# ESP8266_1wire_Gateway_NodeMCU_WeMosD1Min.net
KiCad netlist of a schematic drawn in EAGLE
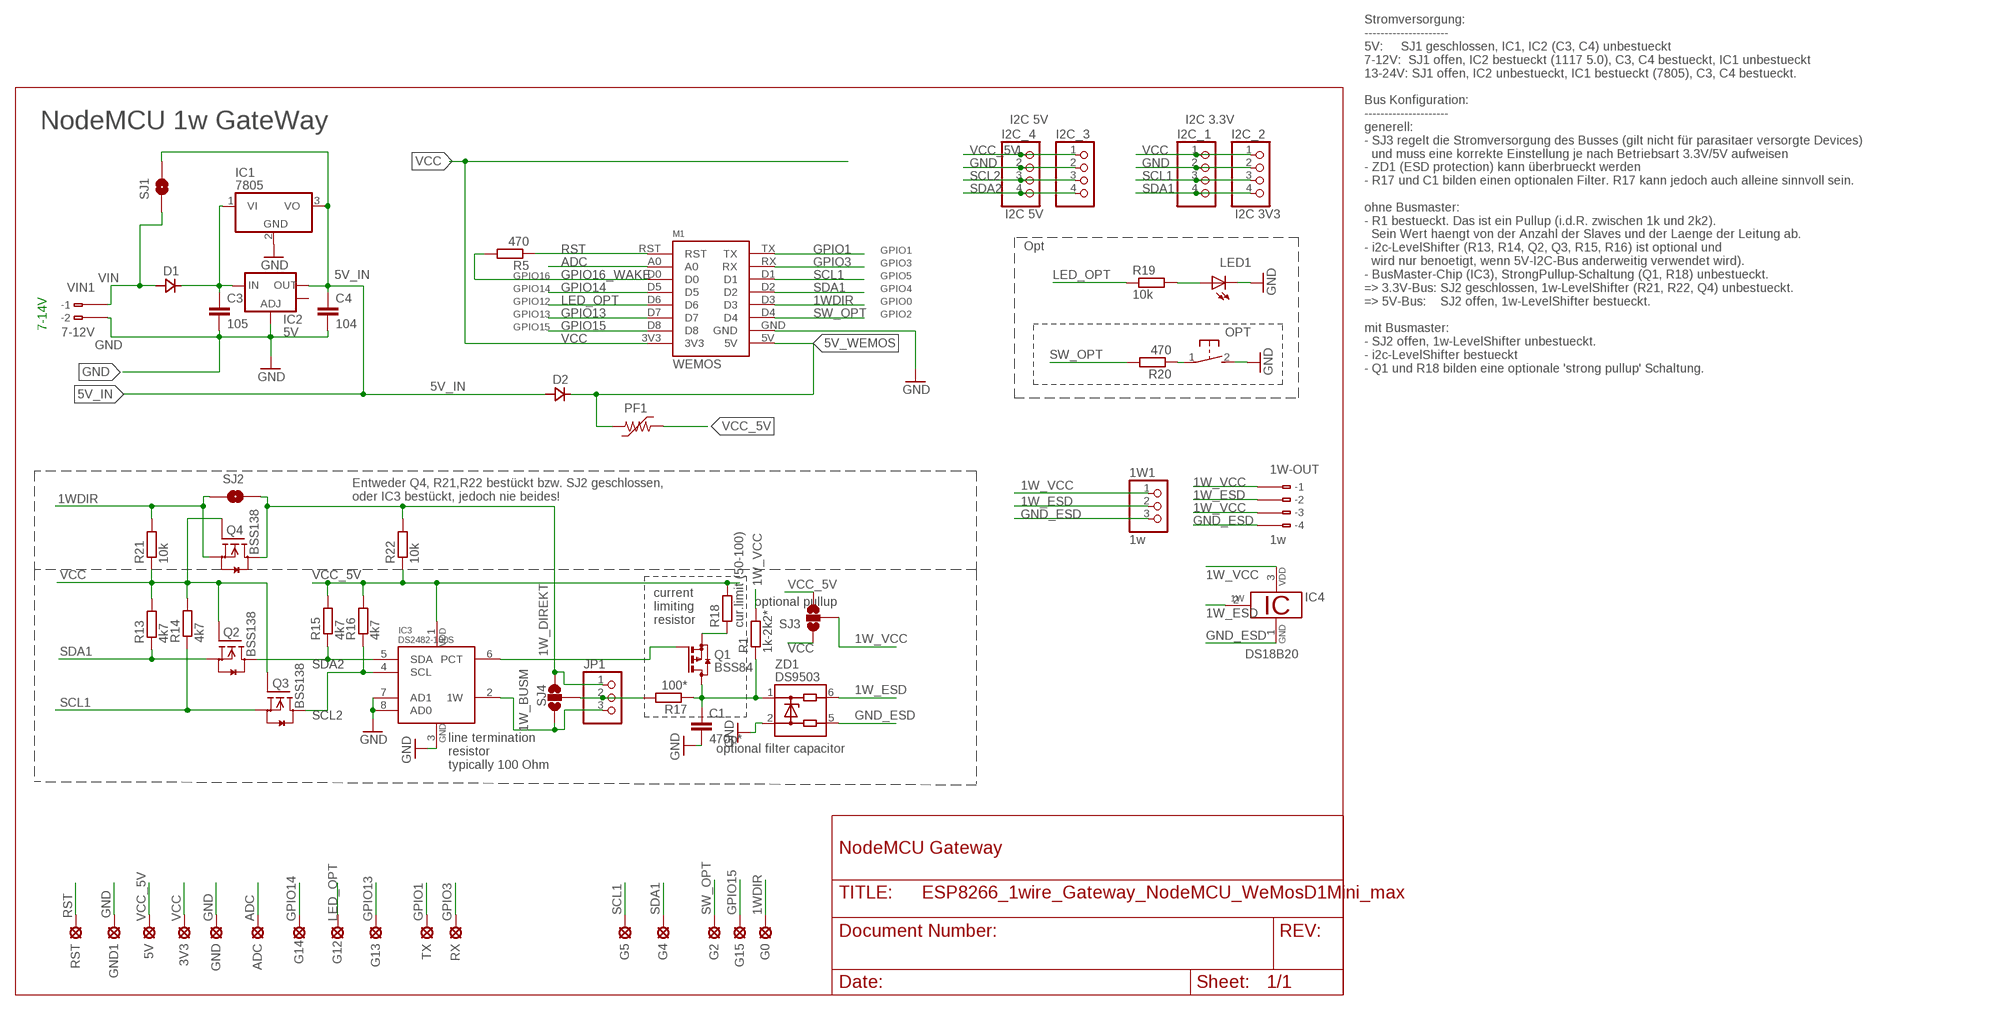
[diagram p0: schematic, sheet 1]

(export (version "E")
  (design (tool "Eeschema 10.0.6"))
  (components
    (comp (ref "1W-OUT")
      (value "1w")
      (footprint "eagle-import:CON_350-104")
      (fields (field (name "MPN") "233-104"))
      (libsource (lib "eagle-import") (part "CON_350-104"))
    )
    (comp (ref "1W1")
      (value "1w")
      (footprint "eagle-import:1X03")
      (libsource (lib "eagle-import") (part "PINHD-1X3_S"))
    )
    (comp (ref "3V3")
      (value "LSP10")
      (footprint "eagle-import:LSP10")
      (libsource (lib "eagle-import") (part "LSP10"))
    )
    (comp (ref "5V")
      (value "LSP10")
      (footprint "eagle-import:LSP10")
      (libsource (lib "eagle-import") (part "LSP10"))
    )
    (comp (ref "ADC")
      (value "LSP10")
      (footprint "eagle-import:LSP10")
      (libsource (lib "eagle-import") (part "LSP10"))
    )
    (comp (ref "C1")
      (value "470p*")
      (footprint "eagle-import:C0805")
      (libsource (lib "eagle-import") (part "C-EUC0805"))
    )
    (comp (ref "C3")
      (value "105")
      (footprint "eagle-import:C0805")
      (libsource (lib "eagle-import") (part "C-EUC0805"))
    )
    (comp (ref "C4")
      (value "104")
      (footprint "eagle-import:C0805")
      (libsource (lib "eagle-import") (part "C-EUC0805"))
    )
    (comp (ref "D1")
      (value "SS14")
      (footprint "eagle-import:DO214")
      (libsource (lib "eagle-import") (part "SS14"))
    )
    (comp (ref "D2")
      (value "SS14")
      (footprint "eagle-import:DO214")
      (libsource (lib "eagle-import") (part "SS14"))
    )
    (comp (ref "G0")
      (value "LSP10")
      (footprint "eagle-import:LSP10")
      (libsource (lib "eagle-import") (part "LSP10"))
    )
    (comp (ref "G2")
      (value "LSP10")
      (footprint "eagle-import:LSP10")
      (libsource (lib "eagle-import") (part "LSP10"))
    )
    (comp (ref "G4")
      (value "LSP10")
      (footprint "eagle-import:LSP10")
      (libsource (lib "eagle-import") (part "LSP10"))
    )
    (comp (ref "G5")
      (value "LSP10")
      (footprint "eagle-import:LSP10")
      (libsource (lib "eagle-import") (part "LSP10"))
    )
    (comp (ref "G12")
      (value "LSP10")
      (footprint "eagle-import:LSP10")
      (libsource (lib "eagle-import") (part "LSP10"))
    )
    (comp (ref "G13")
      (value "LSP10")
      (footprint "eagle-import:LSP10")
      (libsource (lib "eagle-import") (part "LSP10"))
    )
    (comp (ref "G14")
      (value "LSP10")
      (footprint "eagle-import:LSP10")
      (libsource (lib "eagle-import") (part "LSP10"))
    )
    (comp (ref "G15")
      (value "LSP10")
      (footprint "eagle-import:LSP10")
      (libsource (lib "eagle-import") (part "LSP10"))
    )
    (comp (ref "GND")
      (value "LSP10")
      (footprint "eagle-import:LSP10")
      (libsource (lib "eagle-import") (part "LSP10"))
    )
    (comp (ref "GND1")
      (value "GND")
      (footprint "eagle-import:LSP10")
      (libsource (lib "eagle-import") (part "LSP10"))
    )
    (comp (ref "I2C_1")
      (value "PINHD-1X4_S")
      (footprint "eagle-import:1X04")
      (libsource (lib "eagle-import") (part "PINHD-1X4_S"))
    )
    (comp (ref "I2C_2")
      (value "I2C 3V3")
      (footprint "eagle-import:1X04")
      (libsource (lib "eagle-import") (part "PINHD-1X4_S"))
    )
    (comp (ref "I2C_3")
      (value "PINHD-1X4_S")
      (footprint "eagle-import:1X04")
      (libsource (lib "eagle-import") (part "PINHD-1X4_S"))
    )
    (comp (ref "I2C_4")
      (value "I2C 5V")
      (footprint "eagle-import:1X04")
      (libsource (lib "eagle-import") (part "PINHD-1X4_S"))
    )
    (comp (ref "IC1")
      (value "7805")
      (footprint "eagle-import:TO220V")
      (libsource (lib "eagle-import") (part "78TV05"))
    )
    (comp (ref "IC2")
      (value "5V")
      (footprint "eagle-import:SOT223")
      (libsource (lib "eagle-import") (part "V_REG_LM1117SOT223"))
    )
    (comp (ref "IC3")
      (value "DS2482-100S")
      (footprint "eagle-import:SO08")
      (libsource (lib "eagle-import") (part "DS2482-100S"))
    )
    (comp (ref "IC4")
      (value "DS18B20")
      (footprint "eagle-import:TO92-")
      (libsource (lib "eagle-import") (part "DS18B20"))
    )
    (comp (ref "JP1")
      (value "PINHD-1X3_S")
      (footprint "eagle-import:1X03")
      (libsource (lib "eagle-import") (part "PINHD-1X3_S"))
    )
    (comp (ref "LED1")
      (value "CFG")
      (footprint "eagle-import:CHIPLED_1206")
      (libsource (lib "eagle-import") (part "LEDCHIPLED_1206"))
    )
    (comp (ref "M1")
      (value "WEMOS")
      (footprint "eagle-import:WEMOS")
      (libsource (lib "eagle-import") (part "WEMOS"))
    )
    (comp (ref "OPT")
      (value "OPT")
      (footprint "eagle-import:DTSM-3")
      (libsource (lib "eagle-import") (part "DTSM-3"))
    )
    (comp (ref "PF1")
      (value "500mA")
      (footprint "eagle-import:F1206")
      (libsource (lib "eagle-import") (part "PTC-F1206"))
    )
    (comp (ref "Q1")
      (value "BSS84")
      (footprint "eagle-import:SOT23")
      (libsource (lib "eagle-import") (part "BSS84"))
    )
    (comp (ref "Q2")
      (value "BSS138")
      (footprint "eagle-import:SOT23")
      (libsource (lib "eagle-import") (part "BSS138"))
    )
    (comp (ref "Q3")
      (value "BSS138")
      (footprint "eagle-import:SOT23")
      (libsource (lib "eagle-import") (part "BSS138"))
    )
    (comp (ref "Q4")
      (value "BSS138")
      (footprint "eagle-import:SOT23")
      (libsource (lib "eagle-import") (part "BSS138"))
    )
    (comp (ref "R1")
      (value "1k-2k2*")
      (footprint "eagle-import:R0805")
      (libsource (lib "eagle-import") (part "R-EU_R0805"))
    )
    (comp (ref "R5")
      (value "470")
      (footprint "eagle-import:R0805")
      (libsource (lib "eagle-import") (part "resistor_R-EU_R0805"))
    )
    (comp (ref "R13")
      (value "4k7")
      (footprint "eagle-import:R0805")
      (libsource (lib "eagle-import") (part "resistor_R-EU_R0805"))
    )
    (comp (ref "R14")
      (value "4k7")
      (footprint "eagle-import:R0805")
      (libsource (lib "eagle-import") (part "resistor_R-EU_R0805"))
    )
    (comp (ref "R15")
      (value "4k7")
      (footprint "eagle-import:R0805")
      (libsource (lib "eagle-import") (part "resistor_R-EU_R0805"))
    )
    (comp (ref "R16")
      (value "4k7")
      (footprint "eagle-import:R0805")
      (libsource (lib "eagle-import") (part "resistor_R-EU_R0805"))
    )
    (comp (ref "R17")
      (value "100*")
      (footprint "eagle-import:R0805_SMALL_GAP")
      (libsource (lib "eagle-import") (part "R0805_SMALL_GAP"))
    )
    (comp (ref "R18")
      (value "cur.limit (50-100)")
      (footprint "eagle-import:R0805_SMALL_GAP")
      (libsource (lib "eagle-import") (part "R0805_SMALL_GAP"))
    )
    (comp (ref "R19")
      (value "10k")
      (footprint "eagle-import:R0805")
      (libsource (lib "eagle-import") (part "R-EU_R0805"))
    )
    (comp (ref "R20")
      (value "470")
      (footprint "eagle-import:R0805")
      (libsource (lib "eagle-import") (part "resistor_R-EU_R0805"))
    )
    (comp (ref "R21")
      (value "10k")
      (footprint "eagle-import:R0805")
      (libsource (lib "eagle-import") (part "resistor_R-EU_R0805"))
    )
    (comp (ref "R22")
      (value "10k")
      (footprint "eagle-import:R0805")
      (libsource (lib "eagle-import") (part "resistor_R-EU_R0805"))
    )
    (comp (ref "RST")
      (value "RST")
      (footprint "eagle-import:LSP10")
      (libsource (lib "eagle-import") (part "LSP10"))
    )
    (comp (ref "RX")
      (value "LSP10")
      (footprint "eagle-import:LSP10")
      (libsource (lib "eagle-import") (part "LSP10"))
    )
    (comp (ref "SJ1")
      (value "bypass vreg")
      (footprint "eagle-import:PAD-JUMPER-2-NO_YES_SILK")
      (libsource (lib "eagle-import") (part "JUMPER-PAD-2-NOYES_SILK"))
    )
    (comp (ref "SJ2")
      (value "bypass")
      (footprint "eagle-import:PAD-JUMPER-2-NO_YES_SILK")
      (libsource (lib "eagle-import") (part "JUMPER-PAD-2-NOYES_SILK"))
    )
    (comp (ref "SJ3")
      (value "5V | 3V3")
      (footprint "eagle-import:PAD-JUMPER-3-NO_YES_SILK")
      (libsource (lib "eagle-import") (part "JUMPER-PAD-3-NOYES_SILK"))
    )
    (comp (ref "SJ4")
      (value "direct | busmaster")
      (footprint "eagle-import:PAD-JUMPER-3-NO_YES_SILK")
      (libsource (lib "eagle-import") (part "JUMPER-PAD-3-NOYES_SILK"))
    )
    (comp (ref "TX")
      (value "LSP10")
      (footprint "eagle-import:LSP10")
      (libsource (lib "eagle-import") (part "LSP10"))
    )
    (comp (ref "VIN1")
      (value "7-12V")
      (footprint "eagle-import:CON_350-102")
      (fields (field (name "MPN") "233-102"))
      (libsource (lib "eagle-import") (part "CON_350-102"))
    )
    (comp (ref "ZD1")
      (value "DS9503")
      (footprint "eagle-import:TSOC6_BYPASS_J")
      (libsource (lib "eagle-import") (part "DS9503_BYPASS_JP"))
    )
  )
  (nets
    (net (code "1") (name "/1WDIR") (class "Default")
      (node (ref "G0") (pin "1") (pinfunction "MP_1") (pintype "passive"))
      (node (ref "M1") (pin "D3") (pinfunction "D3_D3") (pintype "bidirectional"))
      (node (ref "Q4") (pin "2") (pinfunction "S_2") (pintype "passive"))
      (node (ref "R21") (pin "2") (pinfunction "2_2") (pintype "passive"))
      (node (ref "SJ2") (pin "1") (pinfunction "1_1") (pintype "passive"))
    )
    (net (code "2") (name "/1W_BUSM") (class "Default")
      (node (ref "IC3") (pin "2") (pinfunction "1W_2") (pintype "open_collector"))
      (node (ref "JP1") (pin "3") (pinfunction "3_3") (pintype "passive"))
      (node (ref "SJ4") (pin "1") (pinfunction "1_1") (pintype "passive"))
    )
    (net (code "3") (name "/1W_DIREKT") (class "Default")
      (node (ref "JP1") (pin "1") (pinfunction "1_1") (pintype "passive"))
      (node (ref "Q4") (pin "3") (pinfunction "D_3") (pintype "passive"))
      (node (ref "R22") (pin "2") (pinfunction "2_2") (pintype "passive"))
      (node (ref "SJ2") (pin "2") (pinfunction "2_2") (pintype "passive"))
      (node (ref "SJ4") (pin "3") (pinfunction "3_3") (pintype "passive"))
    )
    (net (code "4") (name "/1W_ESD") (class "Default")
      (node (ref "1W-OUT") (pin "B2") (pinfunction "B-2_B2") (pintype "passive"))
      (node (ref "1W1") (pin "2") (pinfunction "2_2") (pintype "passive"))
      (node (ref "IC4") (pin "2") (pinfunction "1W_2") (pintype "power_in"))
      (node (ref "ZD1") (pin "6") (pinfunction "P$4_6") (pintype "passive"))
    )
    (net (code "5") (name "/1W_VCC") (class "Default")
      (node (ref "1W-OUT") (pin "B1") (pinfunction "B-1_B1") (pintype "passive"))
      (node (ref "1W-OUT") (pin "B3") (pinfunction "B-3_B3") (pintype "passive"))
      (node (ref "1W1") (pin "1") (pinfunction "1_1") (pintype "passive"))
      (node (ref "IC4") (pin "3") (pinfunction "VDD_3") (pintype "power_in"))
      (node (ref "R1") (pin "2") (pinfunction "2_2") (pintype "passive"))
      (node (ref "SJ3") (pin "2") (pinfunction "2_2") (pintype "passive"))
    )
    (net (code "6") (name "/ADC") (class "Default")
      (node (ref "ADC") (pin "1") (pinfunction "MP_1") (pintype "passive"))
      (node (ref "M1") (pin "A0") (pinfunction "A0_A0") (pintype "bidirectional"))
    )
    (net (code "7") (name "/GND_ESD") (class "Default")
      (node (ref "1W-OUT") (pin "B4") (pinfunction "B-4_B4") (pintype "passive"))
      (node (ref "1W1") (pin "3") (pinfunction "3_3") (pintype "passive"))
      (node (ref "IC4") (pin "1") (pinfunction "GND_1") (pintype "power_in"))
      (node (ref "ZD1") (pin "5") (pinfunction "P$3_5") (pintype "passive"))
    )
    (net (code "8") (name "/GPIO1") (class "Default")
      (node (ref "M1") (pin "TX") (pinfunction "TX_TX") (pintype "bidirectional"))
      (node (ref "TX") (pin "1") (pinfunction "MP_1") (pintype "passive"))
    )
    (net (code "9") (name "/GPIO3") (class "Default")
      (node (ref "M1") (pin "RX") (pinfunction "RX_RX") (pintype "bidirectional"))
      (node (ref "RX") (pin "1") (pinfunction "MP_1") (pintype "passive"))
    )
    (net (code "10") (name "/GPIO13") (class "Default")
      (node (ref "G13") (pin "1") (pinfunction "MP_1") (pintype "passive"))
      (node (ref "M1") (pin "D7") (pinfunction "D7_D7") (pintype "bidirectional"))
    )
    (net (code "11") (name "/GPIO14") (class "Default")
      (node (ref "G14") (pin "1") (pinfunction "MP_1") (pintype "passive"))
      (node (ref "M1") (pin "D5") (pinfunction "D5_D5") (pintype "bidirectional"))
    )
    (net (code "12") (name "/GPIO15") (class "Default")
      (node (ref "G15") (pin "1") (pinfunction "MP_1") (pintype "passive"))
      (node (ref "M1") (pin "D8") (pinfunction "D8_D8") (pintype "bidirectional"))
    )
    (net (code "13") (name "/GPIO16_WAKE") (class "Default")
      (node (ref "M1") (pin "D0") (pinfunction "D0_D0") (pintype "bidirectional"))
      (node (ref "R5") (pin "2") (pinfunction "2_2") (pintype "passive"))
    )
    (net (code "14") (name "/LED_OPT") (class "Default")
      (node (ref "G12") (pin "1") (pinfunction "MP_1") (pintype "passive"))
      (node (ref "M1") (pin "D6") (pinfunction "D6_D6") (pintype "bidirectional"))
      (node (ref "R19") (pin "1") (pinfunction "1_1") (pintype "passive"))
    )
    (net (code "15") (name "/RST") (class "Default")
      (node (ref "M1") (pin "RST") (pinfunction "RST_RST") (pintype "bidirectional"))
      (node (ref "R5") (pin "1") (pinfunction "1_1") (pintype "passive"))
      (node (ref "RST") (pin "1") (pinfunction "MP_1") (pintype "passive"))
    )
    (net (code "16") (name "/SCL1") (class "Default")
      (node (ref "G5") (pin "1") (pinfunction "MP_1") (pintype "passive"))
      (node (ref "I2C_1") (pin "3") (pinfunction "3_3") (pintype "passive"))
      (node (ref "I2C_2") (pin "3") (pinfunction "3_3") (pintype "passive"))
      (node (ref "M1") (pin "D1") (pinfunction "D1_D1") (pintype "bidirectional"))
      (node (ref "Q3") (pin "2") (pinfunction "S_2") (pintype "passive"))
      (node (ref "R14") (pin "1") (pinfunction "1_1") (pintype "passive"))
    )
    (net (code "17") (name "/SCL2") (class "Default")
      (node (ref "I2C_3") (pin "3") (pinfunction "3_3") (pintype "passive"))
      (node (ref "I2C_4") (pin "3") (pinfunction "3_3") (pintype "passive"))
      (node (ref "IC3") (pin "4") (pinfunction "SCL_4") (pintype "input"))
      (node (ref "Q3") (pin "3") (pinfunction "D_3") (pintype "passive"))
      (node (ref "R16") (pin "1") (pinfunction "1_1") (pintype "passive"))
    )
    (net (code "18") (name "/SDA1") (class "Default")
      (node (ref "G4") (pin "1") (pinfunction "MP_1") (pintype "passive"))
      (node (ref "I2C_1") (pin "4") (pinfunction "4_4") (pintype "passive"))
      (node (ref "I2C_2") (pin "4") (pinfunction "4_4") (pintype "passive"))
      (node (ref "M1") (pin "D2") (pinfunction "D2_D2") (pintype "bidirectional"))
      (node (ref "Q2") (pin "2") (pinfunction "S_2") (pintype "passive"))
      (node (ref "R13") (pin "1") (pinfunction "1_1") (pintype "passive"))
    )
    (net (code "19") (name "/SDA2") (class "Default")
      (node (ref "I2C_3") (pin "4") (pinfunction "4_4") (pintype "passive"))
      (node (ref "I2C_4") (pin "4") (pinfunction "4_4") (pintype "passive"))
      (node (ref "IC3") (pin "5") (pinfunction "SDA_5") (pintype "bidirectional"))
      (node (ref "Q2") (pin "3") (pinfunction "D_3") (pintype "passive"))
      (node (ref "R15") (pin "1") (pinfunction "1_1") (pintype "passive"))
    )
    (net (code "20") (name "/SW_OPT") (class "Default")
      (node (ref "G2") (pin "1") (pinfunction "MP_1") (pintype "passive"))
      (node (ref "M1") (pin "D4") (pinfunction "D4_D4") (pintype "bidirectional"))
      (node (ref "R20") (pin "2") (pinfunction "2_2") (pintype "passive"))
    )
    (net (code "21") (name "/VIN") (class "Default")
      (node (ref "D1") (pin "ANODE") (pinfunction "ANODE_ANODE") (pintype "bidirectional"))
      (node (ref "SJ1") (pin "1") (pinfunction "1_1") (pintype "passive"))
      (node (ref "VIN1") (pin "B1") (pinfunction "B-1_B1") (pintype "passive"))
    )
    (net (code "22") (name "5V_IN") (class "Default")
      (node (ref "C4") (pin "1") (pinfunction "1_1") (pintype "passive"))
      (node (ref "D2") (pin "ANODE") (pinfunction "ANODE_ANODE") (pintype "bidirectional"))
      (node (ref "IC1") (pin "3") (pinfunction "VO_3") (pintype "passive"))
      (node (ref "IC2") (pin "2") (pinfunction "OUT_2") (pintype "output"))
      (node (ref "SJ1") (pin "2") (pinfunction "2_2") (pintype "passive"))
    )
    (net (code "23") (name "5V_WEMOS") (class "Default")
      (node (ref "D2") (pin "CATHODE") (pinfunction "CATHODE_CATHODE") (pintype "bidirectional"))
      (node (ref "M1") (pin "5V") (pinfunction "5V_5V") (pintype "bidirectional"))
      (node (ref "PF1") (pin "2") (pinfunction "2_2") (pintype "passive"))
    )
    (net (code "24") (name "GND") (class "Default")
      (node (ref "C1") (pin "2") (pinfunction "2_2") (pintype "passive"))
      (node (ref "C3") (pin "2") (pinfunction "2_2") (pintype "passive"))
      (node (ref "C4") (pin "2") (pinfunction "2_2") (pintype "passive"))
      (node (ref "GND") (pin "1") (pinfunction "MP_1") (pintype "passive"))
      (node (ref "GND1") (pin "1") (pinfunction "MP_1") (pintype "passive"))
      (node (ref "I2C_1") (pin "2") (pinfunction "2_2") (pintype "passive"))
      (node (ref "I2C_2") (pin "2") (pinfunction "2_2") (pintype "passive"))
      (node (ref "I2C_3") (pin "2") (pinfunction "2_2") (pintype "passive"))
      (node (ref "I2C_4") (pin "2") (pinfunction "2_2") (pintype "passive"))
      (node (ref "IC1") (pin "2") (pinfunction "GND_2") (pintype "passive"))
      (node (ref "IC2") (pin "1") (pinfunction "ADJ_1") (pintype "input"))
      (node (ref "IC3") (pin "3") (pinfunction "GND_3") (pintype "power_in"))
      (node (ref "IC3") (pin "7") (pinfunction "AD1_7") (pintype "input"))
      (node (ref "IC3") (pin "8") (pinfunction "AD0_8") (pintype "input"))
      (node (ref "LED1") (pin "C") (pinfunction "C_C") (pintype "passive"))
      (node (ref "M1") (pin "GND") (pinfunction "GND_GND") (pintype "bidirectional"))
      (node (ref "OPT") (pin "2") (pinfunction "2_2") (pintype "passive"))
      (node (ref "VIN1") (pin "B2") (pinfunction "B-2_B2") (pintype "passive"))
      (node (ref "ZD1") (pin "2") (pinfunction "P$2_2") (pintype "passive"))
    )
    (net (code "25") (name "Net-(IC1-VI)") (class "Default")
      (node (ref "C3") (pin "1") (pinfunction "1_1") (pintype "passive"))
      (node (ref "D1") (pin "CATHODE") (pinfunction "CATHODE_CATHODE") (pintype "bidirectional"))
      (node (ref "IC1") (pin "1") (pinfunction "VI_1") (pintype "input"))
      (node (ref "IC2") (pin "3") (pinfunction "IN_3") (pintype "input"))
    )
    (net (code "26") (name "Net-(IC3-PCT)") (class "Default")
      (node (ref "IC3") (pin "6") (pinfunction "PCT_6") (pintype "output"))
      (node (ref "Q1") (pin "1") (pinfunction "G_1") (pintype "passive"))
    )
    (net (code "27") (name "Net-(JP1-Pad2)") (class "Default")
      (node (ref "JP1") (pin "2") (pinfunction "2_2") (pintype "passive"))
      (node (ref "R17") (pin "2") (pinfunction "2_2") (pintype "passive"))
      (node (ref "SJ4") (pin "2") (pinfunction "2_2") (pintype "passive"))
    )
    (net (code "28") (name "Net-(LED1-PadA)") (class "Default")
      (node (ref "LED1") (pin "A") (pinfunction "A_A") (pintype "passive"))
      (node (ref "R19") (pin "2") (pinfunction "2_2") (pintype "passive"))
    )
    (net (code "29") (name "Net-(OPT-Pad1)") (class "Default")
      (node (ref "OPT") (pin "1") (pinfunction "1_1") (pintype "passive"))
      (node (ref "R20") (pin "1") (pinfunction "1_1") (pintype "passive"))
    )
    (net (code "30") (name "Net-(Q1-D)") (class "Default")
      (node (ref "C1") (pin "1") (pinfunction "1_1") (pintype "passive"))
      (node (ref "Q1") (pin "3") (pinfunction "D_3") (pintype "passive"))
      (node (ref "R1") (pin "1") (pinfunction "1_1") (pintype "passive"))
      (node (ref "R17") (pin "1") (pinfunction "1_1") (pintype "passive"))
      (node (ref "ZD1") (pin "1") (pinfunction "P$1_1") (pintype "passive"))
    )
    (net (code "31") (name "Net-(Q1-S)") (class "Default")
      (node (ref "Q1") (pin "2") (pinfunction "S_2") (pintype "passive"))
      (node (ref "R18") (pin "1") (pinfunction "1_1") (pintype "passive"))
    )
    (net (code "32") (name "VCC") (class "Default")
      (node (ref "3V3") (pin "1") (pinfunction "MP_1") (pintype "passive"))
      (node (ref "I2C_1") (pin "1") (pinfunction "1_1") (pintype "passive"))
      (node (ref "I2C_2") (pin "1") (pinfunction "1_1") (pintype "passive"))
      (node (ref "M1") (pin "3V3") (pinfunction "3V3_3V3") (pintype "bidirectional"))
      (node (ref "Q2") (pin "1") (pinfunction "G_1") (pintype "passive"))
      (node (ref "Q3") (pin "1") (pinfunction "G_1") (pintype "passive"))
      (node (ref "Q4") (pin "1") (pinfunction "G_1") (pintype "passive"))
      (node (ref "R13") (pin "2") (pinfunction "2_2") (pintype "passive"))
      (node (ref "R14") (pin "2") (pinfunction "2_2") (pintype "passive"))
      (node (ref "R21") (pin "1") (pinfunction "1_1") (pintype "passive"))
      (node (ref "SJ3") (pin "1") (pinfunction "1_1") (pintype "passive"))
    )
    (net (code "33") (name "VCC_5V") (class "Default")
      (node (ref "5V") (pin "1") (pinfunction "MP_1") (pintype "passive"))
      (node (ref "I2C_3") (pin "1") (pinfunction "1_1") (pintype "passive"))
      (node (ref "I2C_4") (pin "1") (pinfunction "1_1") (pintype "passive"))
      (node (ref "IC3") (pin "1") (pinfunction "VDD_1") (pintype "power_in"))
      (node (ref "PF1") (pin "1") (pinfunction "1_1") (pintype "passive"))
      (node (ref "R15") (pin "2") (pinfunction "2_2") (pintype "passive"))
      (node (ref "R16") (pin "2") (pinfunction "2_2") (pintype "passive"))
      (node (ref "R18") (pin "2") (pinfunction "2_2") (pintype "passive"))
      (node (ref "R22") (pin "1") (pinfunction "1_1") (pintype "passive"))
      (node (ref "SJ3") (pin "3") (pinfunction "3_3") (pintype "passive"))
    )
    (net (code "34") (name "unconnected-(1W-OUT--1-PadA1)") (class "Default")
      (node (ref "1W-OUT") (pin "A1") (pinfunction "-1_A1") (pintype "passive"))
    )
    (net (code "35") (name "unconnected-(1W-OUT--2-PadA2)") (class "Default")
      (node (ref "1W-OUT") (pin "A2") (pinfunction "-2_A2") (pintype "passive"))
    )
    (net (code "36") (name "unconnected-(1W-OUT--3-PadA3)") (class "Default")
      (node (ref "1W-OUT") (pin "A3") (pinfunction "-3_A3") (pintype "passive"))
    )
    (net (code "37") (name "unconnected-(1W-OUT--4-PadA4)") (class "Default")
      (node (ref "1W-OUT") (pin "A4") (pinfunction "-4_A4") (pintype "passive"))
    )
    (net (code "38") (name "unconnected-(IC2-OUT-Pad4)") (class "Default")
      (node (ref "IC2") (pin "4") (pinfunction "OUT_4") (pintype "output"))
    )
    (net (code "39") (name "unconnected-(VIN1--1-PadA1)") (class "Default")
      (node (ref "VIN1") (pin "A1") (pinfunction "-1_A1") (pintype "passive"))
    )
    (net (code "40") (name "unconnected-(VIN1--2-PadA2)") (class "Default")
      (node (ref "VIN1") (pin "A2") (pinfunction "-2_A2") (pintype "passive"))
    )
  )
)
